# Van_Atta_array.net
KiCad netlist of a schematic drawn in Altium Designer
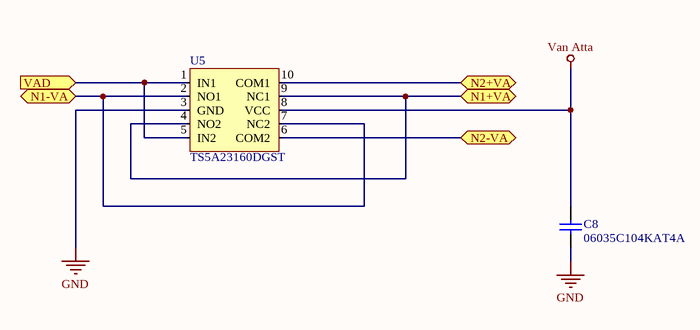
[diagram p0: Van Atta array.SchDoc]

(export (version "E")
  (design (tool "Eeschema 10.0.6"))
  (components
    (comp (ref "C8")
      (value "06035C104KAT4A")
      (footprint "CAPC1608X90X35LL15T15")
      (fields (field (name "MANUFACTURER") "AVX Interconnect / Elco"))
      (libsource (lib "Altium Content Vault") (part "CAP"))
    )
    (comp (ref "U5")
      (value "TS5A23160DGST")
      (footprint "TSSOP50P490X110-10N")
      (description "0.9-Ω on-state resistance, 5-V, 2: 1 (SPDT), 2-channel analog switch 10-VSSOP -40 to 85")
      (libsource (lib "Nick") (part "TS5A23160DGST-Symbol-1"))
    )
  )
  (nets
    (net (code "1") (name "/N1+VA") (class "Default")
      (node (ref "U5") (pin "4") (pinfunction "NO2_4") (pintype "bidirectional"))
      (node (ref "U5") (pin "9") (pinfunction "NC1_9") (pintype "bidirectional"))
    )
    (net (code "2") (name "/N1-VA") (class "Default")
      (node (ref "U5") (pin "2") (pinfunction "NO1_2") (pintype "bidirectional"))
      (node (ref "U5") (pin "7") (pinfunction "NC2_7") (pintype "bidirectional"))
    )
    (net (code "3") (name "/N2+VA") (class "Default")
      (node (ref "U5") (pin "10") (pinfunction "COM1_10") (pintype "bidirectional"))
    )
    (net (code "4") (name "/N2-VA") (class "Default")
      (node (ref "U5") (pin "6") (pinfunction "COM2_6") (pintype "bidirectional"))
    )
    (net (code "5") (name "/VAD") (class "Default")
      (node (ref "U5") (pin "1") (pinfunction "IN1_1") (pintype "input"))
      (node (ref "U5") (pin "5") (pinfunction "IN2_5") (pintype "input"))
    )
    (net (code "6") (name "GND") (class "Default")
      (node (ref "C8") (pin "2") (pinfunction "2_2") (pintype "passive"))
      (node (ref "U5") (pin "3") (pinfunction "GND_3") (pintype "power_in"))
    )
    (net (code "7") (name "Van Atta") (class "Default")
      (node (ref "C8") (pin "1") (pinfunction "1_1") (pintype "passive"))
      (node (ref "U5") (pin "8") (pinfunction "VCC_8") (pintype "power_in"))
    )
  )
)
